# Ram_Upgrade.net
KiCad netlist of a schematic drawn in EAGLE
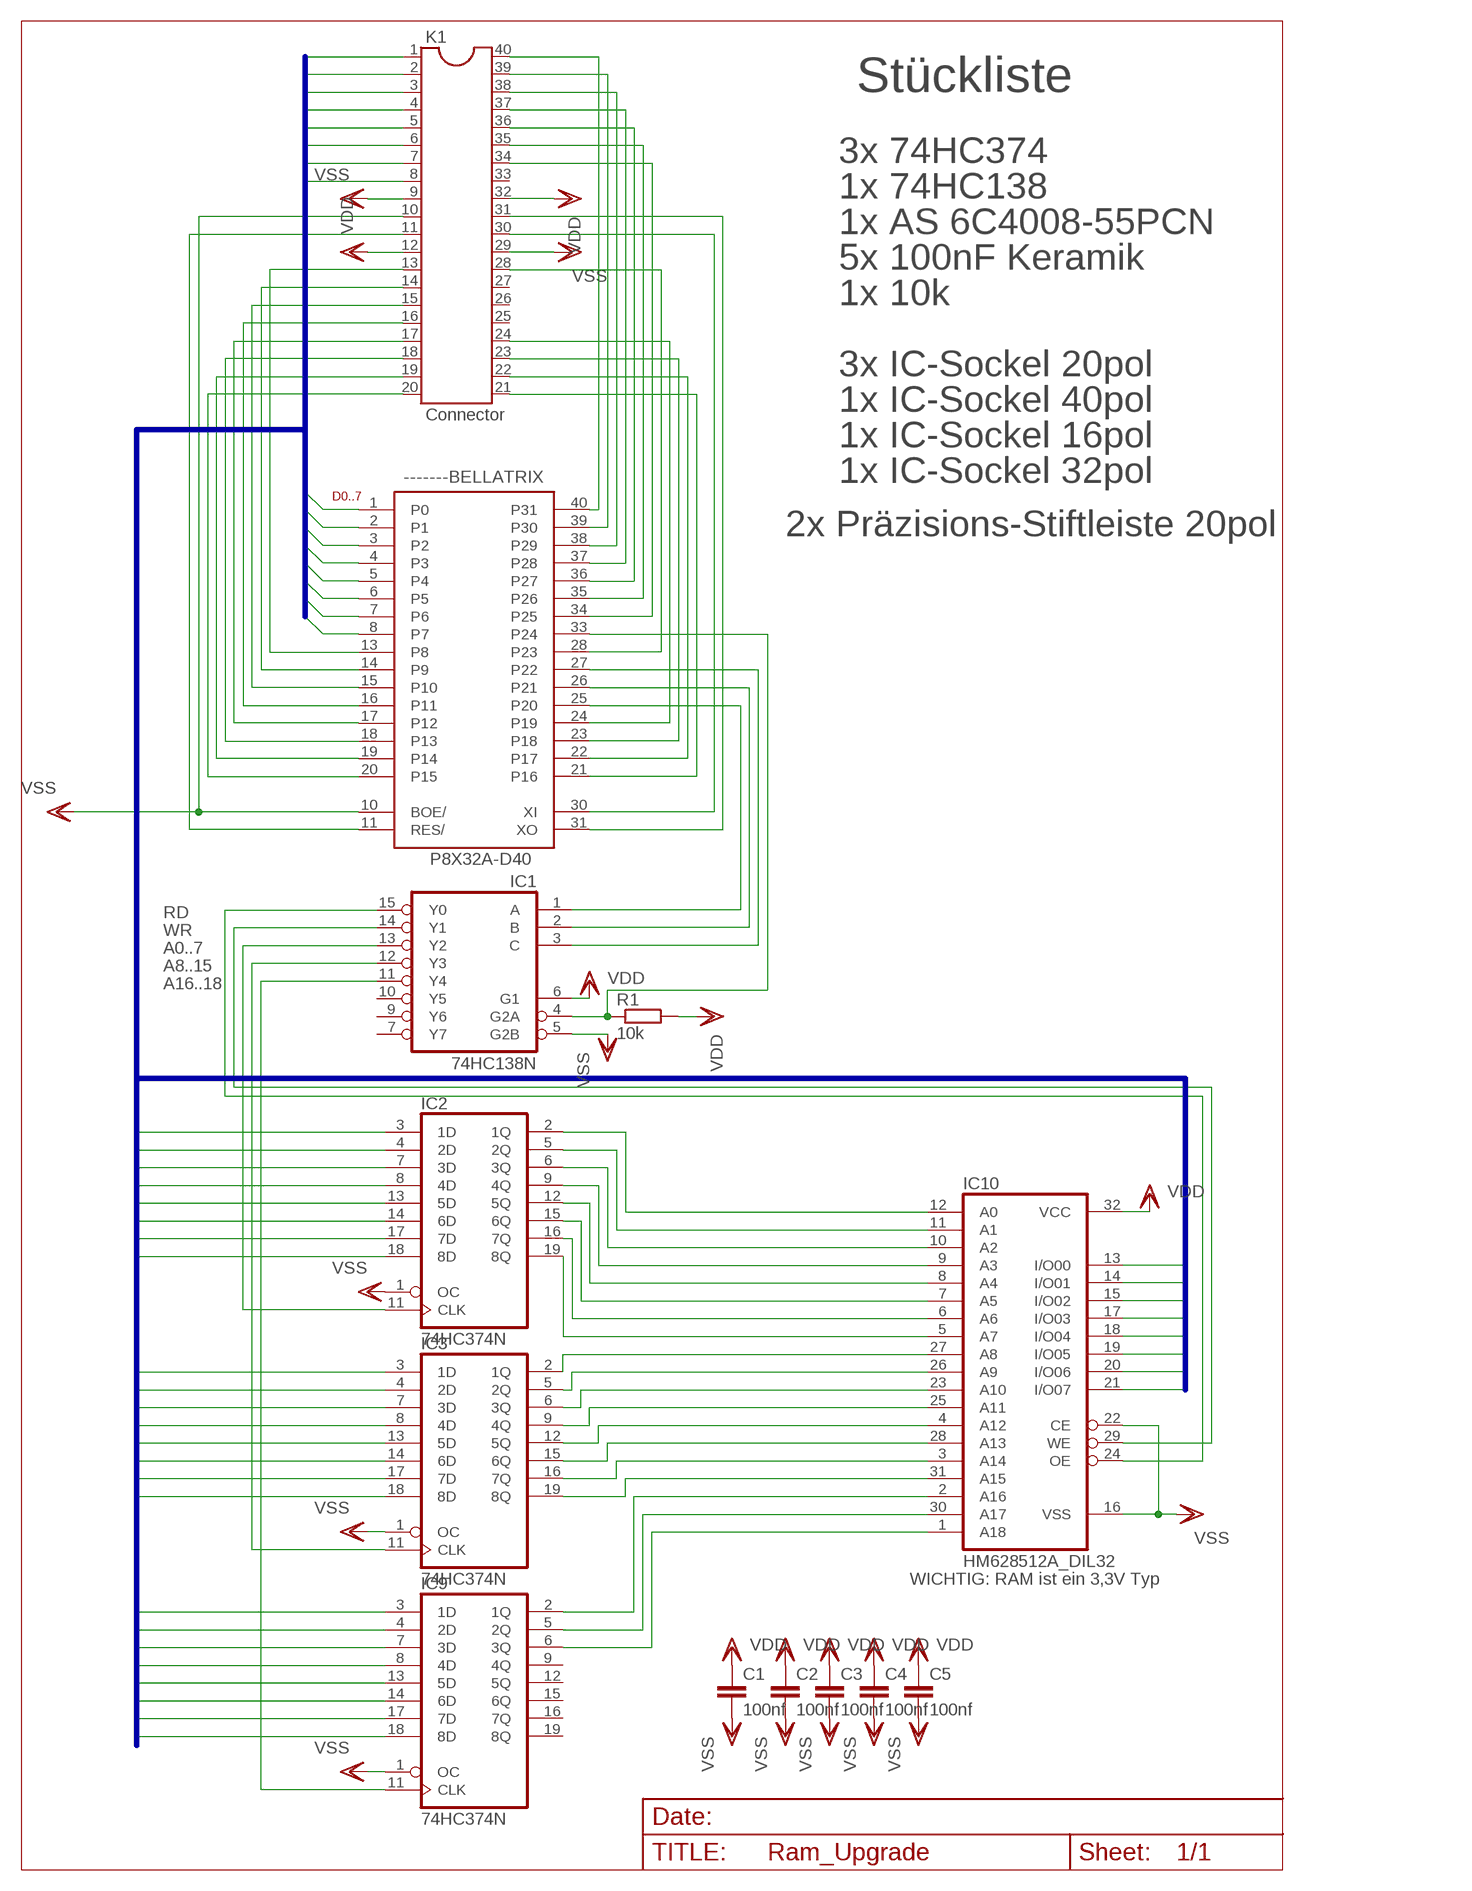
[diagram p0: schematic, sheet 1]

(export (version "E")
  (design (tool "Eeschema 10.0.6"))
  (components
    (comp (ref "-------BELLATRIX")
      (value "P8X32A-D40")
      (footprint "eagle-import:P8X32A-D40")
      (libsource (lib "eagle-import") (part "P8X32A-D40"))
    )
    (comp (ref "C1")
      (value "100nf")
      (footprint "eagle-import:C075-032X103")
      (libsource (lib "eagle-import") (part "C-EU075-032X103"))
    )
    (comp (ref "C2")
      (value "100nf")
      (footprint "eagle-import:C075-032X103")
      (libsource (lib "eagle-import") (part "C-EU075-032X103"))
    )
    (comp (ref "C3")
      (value "100nf")
      (footprint "eagle-import:C075-032X103")
      (libsource (lib "eagle-import") (part "C-EU075-032X103"))
    )
    (comp (ref "C4")
      (value "100nf")
      (footprint "eagle-import:C075-032X103")
      (libsource (lib "eagle-import") (part "C-EU075-032X103"))
    )
    (comp (ref "C5")
      (value "100nf")
      (footprint "eagle-import:C075-032X103")
      (libsource (lib "eagle-import") (part "C-EU075-032X103"))
    )
    (comp (ref "IC1")
      (value "74HC138N")
      (footprint "eagle-import:DIL16")
      (libsource (lib "eagle-import") (part "74138NHC"))
    )
    (comp (ref "IC2")
      (value "74HC374N")
      (footprint "eagle-import:DIL20")
      (libsource (lib "eagle-import") (part "74374NHC"))
    )
    (comp (ref "IC3")
      (value "74HC374N")
      (footprint "eagle-import:DIL20")
      (libsource (lib "eagle-import") (part "74374NHC"))
    )
    (comp (ref "IC9")
      (value "74HC374N")
      (footprint "eagle-import:DIL20")
      (libsource (lib "eagle-import") (part "74374NHC"))
    )
    (comp (ref "IC10")
      (value "HM628512A_DIL32")
      (footprint "eagle-import:DIL32")
      (libsource (lib "eagle-import") (part "HM628512A_DIL32"))
    )
    (comp (ref "K1")
      (value "Connector")
      (footprint "eagle-import:DIL40")
      (libsource (lib "eagle-import") (part "DIL40"))
    )
    (comp (ref "R1")
      (value "10k")
      (footprint "eagle-import:0207_10")
      (libsource (lib "eagle-import") (part "R-EU_0207/10"))
    )
  )
  (nets
    (net (code "1") (name "/D0") (class "Default")
      (node (ref "-------BELLATRIX") (pin "1") (pinfunction "P0_1") (pintype "bidirectional"))
      (node (ref "IC10") (pin "13") (pinfunction "I/O00_13") (pintype "bidirectional"))
      (node (ref "IC2") (pin "3") (pinfunction "1D_3") (pintype "input"))
      (node (ref "IC3") (pin "3") (pinfunction "1D_3") (pintype "input"))
      (node (ref "IC9") (pin "3") (pinfunction "1D_3") (pintype "input"))
      (node (ref "K1") (pin "1") (pinfunction "1_1") (pintype "passive"))
    )
    (net (code "2") (name "/D1") (class "Default")
      (node (ref "-------BELLATRIX") (pin "2") (pinfunction "P1_2") (pintype "bidirectional"))
      (node (ref "IC10") (pin "14") (pinfunction "I/O01_14") (pintype "bidirectional"))
      (node (ref "IC2") (pin "4") (pinfunction "2D_4") (pintype "input"))
      (node (ref "IC3") (pin "4") (pinfunction "2D_4") (pintype "input"))
      (node (ref "IC9") (pin "4") (pinfunction "2D_4") (pintype "input"))
      (node (ref "K1") (pin "2") (pinfunction "2_2") (pintype "passive"))
    )
    (net (code "3") (name "/D2") (class "Default")
      (node (ref "-------BELLATRIX") (pin "3") (pinfunction "P2_3") (pintype "bidirectional"))
      (node (ref "IC10") (pin "15") (pinfunction "I/O02_15") (pintype "bidirectional"))
      (node (ref "IC2") (pin "7") (pinfunction "3D_7") (pintype "input"))
      (node (ref "IC3") (pin "7") (pinfunction "3D_7") (pintype "input"))
      (node (ref "IC9") (pin "7") (pinfunction "3D_7") (pintype "input"))
      (node (ref "K1") (pin "3") (pinfunction "3_3") (pintype "passive"))
    )
    (net (code "4") (name "/D3") (class "Default")
      (node (ref "-------BELLATRIX") (pin "4") (pinfunction "P3_4") (pintype "bidirectional"))
      (node (ref "IC10") (pin "17") (pinfunction "I/O03_17") (pintype "bidirectional"))
      (node (ref "IC2") (pin "8") (pinfunction "4D_8") (pintype "input"))
      (node (ref "IC3") (pin "8") (pinfunction "4D_8") (pintype "input"))
      (node (ref "IC9") (pin "8") (pinfunction "4D_8") (pintype "input"))
      (node (ref "K1") (pin "4") (pinfunction "4_4") (pintype "passive"))
    )
    (net (code "5") (name "/D4") (class "Default")
      (node (ref "-------BELLATRIX") (pin "5") (pinfunction "P4_5") (pintype "bidirectional"))
      (node (ref "IC10") (pin "18") (pinfunction "I/O04_18") (pintype "bidirectional"))
      (node (ref "IC2") (pin "13") (pinfunction "5D_13") (pintype "input"))
      (node (ref "IC3") (pin "13") (pinfunction "5D_13") (pintype "input"))
      (node (ref "IC9") (pin "13") (pinfunction "5D_13") (pintype "input"))
      (node (ref "K1") (pin "5") (pinfunction "5_5") (pintype "passive"))
    )
    (net (code "6") (name "/D5") (class "Default")
      (node (ref "-------BELLATRIX") (pin "6") (pinfunction "P5_6") (pintype "bidirectional"))
      (node (ref "IC10") (pin "19") (pinfunction "I/O05_19") (pintype "bidirectional"))
      (node (ref "IC2") (pin "14") (pinfunction "6D_14") (pintype "input"))
      (node (ref "IC3") (pin "14") (pinfunction "6D_14") (pintype "input"))
      (node (ref "IC9") (pin "14") (pinfunction "6D_14") (pintype "input"))
      (node (ref "K1") (pin "6") (pinfunction "6_6") (pintype "passive"))
    )
    (net (code "7") (name "/D6") (class "Default")
      (node (ref "-------BELLATRIX") (pin "7") (pinfunction "P6_7") (pintype "bidirectional"))
      (node (ref "IC10") (pin "20") (pinfunction "I/O06_20") (pintype "bidirectional"))
      (node (ref "IC2") (pin "17") (pinfunction "7D_17") (pintype "input"))
      (node (ref "IC3") (pin "17") (pinfunction "7D_17") (pintype "input"))
      (node (ref "IC9") (pin "17") (pinfunction "7D_17") (pintype "input"))
      (node (ref "K1") (pin "7") (pinfunction "7_7") (pintype "passive"))
    )
    (net (code "8") (name "/D7") (class "Default")
      (node (ref "-------BELLATRIX") (pin "8") (pinfunction "P7_8") (pintype "bidirectional"))
      (node (ref "IC10") (pin "21") (pinfunction "I/O07_21") (pintype "bidirectional"))
      (node (ref "IC2") (pin "18") (pinfunction "8D_18") (pintype "input"))
      (node (ref "IC3") (pin "18") (pinfunction "8D_18") (pintype "input"))
      (node (ref "IC9") (pin "18") (pinfunction "8D_18") (pintype "input"))
      (node (ref "K1") (pin "8") (pinfunction "8_8") (pintype "passive"))
    )
    (net (code "9") (name "Net-(-------BELLATRIXB-P8)") (class "Default")
      (node (ref "-------BELLATRIX") (pin "13") (pinfunction "P8_13") (pintype "bidirectional"))
      (node (ref "K1") (pin "13") (pinfunction "13_13") (pintype "passive"))
    )
    (net (code "10") (name "Net-(-------BELLATRIXB-P9)") (class "Default")
      (node (ref "-------BELLATRIX") (pin "14") (pinfunction "P9_14") (pintype "bidirectional"))
      (node (ref "K1") (pin "14") (pinfunction "14_14") (pintype "passive"))
    )
    (net (code "11") (name "Net-(-------BELLATRIXB-P10)") (class "Default")
      (node (ref "-------BELLATRIX") (pin "15") (pinfunction "P10_15") (pintype "bidirectional"))
      (node (ref "K1") (pin "15") (pinfunction "15_15") (pintype "passive"))
    )
    (net (code "12") (name "Net-(-------BELLATRIXB-P11)") (class "Default")
      (node (ref "-------BELLATRIX") (pin "16") (pinfunction "P11_16") (pintype "bidirectional"))
      (node (ref "K1") (pin "16") (pinfunction "16_16") (pintype "passive"))
    )
    (net (code "13") (name "Net-(-------BELLATRIXB-P12)") (class "Default")
      (node (ref "-------BELLATRIX") (pin "17") (pinfunction "P12_17") (pintype "bidirectional"))
      (node (ref "K1") (pin "17") (pinfunction "17_17") (pintype "passive"))
    )
    (net (code "14") (name "Net-(-------BELLATRIXB-P13)") (class "Default")
      (node (ref "-------BELLATRIX") (pin "18") (pinfunction "P13_18") (pintype "bidirectional"))
      (node (ref "K1") (pin "18") (pinfunction "18_18") (pintype "passive"))
    )
    (net (code "15") (name "Net-(-------BELLATRIXB-P14)") (class "Default")
      (node (ref "-------BELLATRIX") (pin "19") (pinfunction "P14_19") (pintype "bidirectional"))
      (node (ref "K1") (pin "19") (pinfunction "19_19") (pintype "passive"))
    )
    (net (code "16") (name "Net-(-------BELLATRIXB-P15)") (class "Default")
      (node (ref "-------BELLATRIX") (pin "20") (pinfunction "P15_20") (pintype "bidirectional"))
      (node (ref "K1") (pin "20") (pinfunction "20_20") (pintype "passive"))
    )
    (net (code "17") (name "Net-(-------BELLATRIXB-P16)") (class "Default")
      (node (ref "-------BELLATRIX") (pin "21") (pinfunction "P16_21") (pintype "bidirectional"))
      (node (ref "K1") (pin "21") (pinfunction "21_21") (pintype "passive"))
    )
    (net (code "18") (name "Net-(-------BELLATRIXB-P17)") (class "Default")
      (node (ref "-------BELLATRIX") (pin "22") (pinfunction "P17_22") (pintype "bidirectional"))
      (node (ref "K1") (pin "22") (pinfunction "22_22") (pintype "passive"))
    )
    (net (code "19") (name "Net-(-------BELLATRIXB-P18)") (class "Default")
      (node (ref "-------BELLATRIX") (pin "23") (pinfunction "P18_23") (pintype "bidirectional"))
      (node (ref "K1") (pin "23") (pinfunction "23_23") (pintype "passive"))
    )
    (net (code "20") (name "Net-(-------BELLATRIXB-P19)") (class "Default")
      (node (ref "-------BELLATRIX") (pin "24") (pinfunction "P19_24") (pintype "bidirectional"))
      (node (ref "K1") (pin "24") (pinfunction "24_24") (pintype "passive"))
    )
    (net (code "21") (name "Net-(-------BELLATRIXB-P20)") (class "Default")
      (node (ref "-------BELLATRIX") (pin "25") (pinfunction "P20_25") (pintype "bidirectional"))
      (node (ref "IC1") (pin "1") (pinfunction "A_1") (pintype "input"))
    )
    (net (code "22") (name "Net-(-------BELLATRIXB-P21)") (class "Default")
      (node (ref "-------BELLATRIX") (pin "26") (pinfunction "P21_26") (pintype "bidirectional"))
      (node (ref "IC1") (pin "2") (pinfunction "B_2") (pintype "input"))
    )
    (net (code "23") (name "Net-(-------BELLATRIXB-P22)") (class "Default")
      (node (ref "-------BELLATRIX") (pin "27") (pinfunction "P22_27") (pintype "bidirectional"))
      (node (ref "IC1") (pin "3") (pinfunction "C_3") (pintype "input"))
    )
    (net (code "24") (name "Net-(-------BELLATRIXB-P23)") (class "Default")
      (node (ref "-------BELLATRIX") (pin "28") (pinfunction "P23_28") (pintype "bidirectional"))
      (node (ref "K1") (pin "28") (pinfunction "28_28") (pintype "passive"))
    )
    (net (code "25") (name "Net-(-------BELLATRIXB-P24)") (class "Default")
      (node (ref "-------BELLATRIX") (pin "33") (pinfunction "P24_33") (pintype "bidirectional"))
      (node (ref "IC1") (pin "4") (pinfunction "G2A_4") (pintype "input"))
      (node (ref "R1") (pin "1") (pinfunction "1_1") (pintype "passive"))
    )
    (net (code "26") (name "Net-(-------BELLATRIXB-P25)") (class "Default")
      (node (ref "-------BELLATRIX") (pin "34") (pinfunction "P25_34") (pintype "bidirectional"))
      (node (ref "K1") (pin "34") (pinfunction "34_34") (pintype "passive"))
    )
    (net (code "27") (name "Net-(-------BELLATRIXB-P26)") (class "Default")
      (node (ref "-------BELLATRIX") (pin "35") (pinfunction "P26_35") (pintype "bidirectional"))
      (node (ref "K1") (pin "35") (pinfunction "35_35") (pintype "passive"))
    )
    (net (code "28") (name "Net-(-------BELLATRIXB-P27)") (class "Default")
      (node (ref "-------BELLATRIX") (pin "36") (pinfunction "P27_36") (pintype "bidirectional"))
      (node (ref "K1") (pin "36") (pinfunction "36_36") (pintype "passive"))
    )
    (net (code "29") (name "Net-(-------BELLATRIXB-P28)") (class "Default")
      (node (ref "-------BELLATRIX") (pin "37") (pinfunction "P28_37") (pintype "bidirectional"))
      (node (ref "K1") (pin "37") (pinfunction "37_37") (pintype "passive"))
    )
    (net (code "30") (name "Net-(-------BELLATRIXB-P29)") (class "Default")
      (node (ref "-------BELLATRIX") (pin "38") (pinfunction "P29_38") (pintype "bidirectional"))
      (node (ref "K1") (pin "38") (pinfunction "38_38") (pintype "passive"))
    )
    (net (code "31") (name "Net-(-------BELLATRIXB-P30)") (class "Default")
      (node (ref "-------BELLATRIX") (pin "39") (pinfunction "P30_39") (pintype "bidirectional"))
      (node (ref "K1") (pin "39") (pinfunction "39_39") (pintype "passive"))
    )
    (net (code "32") (name "Net-(-------BELLATRIXB-P31)") (class "Default")
      (node (ref "-------BELLATRIX") (pin "40") (pinfunction "P31_40") (pintype "bidirectional"))
      (node (ref "K1") (pin "40") (pinfunction "40_40") (pintype "passive"))
    )
    (net (code "33") (name "Net-(-------BELLATRIXB-RES{slash})") (class "Default")
      (node (ref "-------BELLATRIX") (pin "11") (pinfunction "RES/_11") (pintype "bidirectional"))
      (node (ref "K1") (pin "11") (pinfunction "11_11") (pintype "passive"))
    )
    (net (code "34") (name "Net-(-------BELLATRIXB-XI)") (class "Default")
      (node (ref "-------BELLATRIX") (pin "30") (pinfunction "XI_30") (pintype "input"))
      (node (ref "K1") (pin "30") (pinfunction "30_30") (pintype "passive"))
    )
    (net (code "35") (name "Net-(-------BELLATRIXB-XO)") (class "Default")
      (node (ref "-------BELLATRIX") (pin "31") (pinfunction "XO_31") (pintype "output"))
      (node (ref "K1") (pin "31") (pinfunction "31_31") (pintype "passive"))
    )
    (net (code "36") (name "Net-(IC1A-Y2)") (class "Default")
      (node (ref "IC1") (pin "13") (pinfunction "Y2_13") (pintype "output"))
      (node (ref "IC2") (pin "11") (pinfunction "CLK_11") (pintype "input"))
    )
    (net (code "37") (name "Net-(IC1A-Y3)") (class "Default")
      (node (ref "IC1") (pin "12") (pinfunction "Y3_12") (pintype "output"))
      (node (ref "IC3") (pin "11") (pinfunction "CLK_11") (pintype "input"))
    )
    (net (code "38") (name "Net-(IC1A-Y4)") (class "Default")
      (node (ref "IC1") (pin "11") (pinfunction "Y4_11") (pintype "output"))
      (node (ref "IC9") (pin "11") (pinfunction "CLK_11") (pintype "input"))
    )
    (net (code "39") (name "Net-(IC10-A0)") (class "Default")
      (node (ref "IC10") (pin "12") (pinfunction "A0_12") (pintype "input"))
      (node (ref "IC2") (pin "2") (pinfunction "1Q_2") (pintype "tri_state"))
    )
    (net (code "40") (name "Net-(IC10-A1)") (class "Default")
      (node (ref "IC10") (pin "11") (pinfunction "A1_11") (pintype "input"))
      (node (ref "IC2") (pin "5") (pinfunction "2Q_5") (pintype "tri_state"))
    )
    (net (code "41") (name "Net-(IC10-A2)") (class "Default")
      (node (ref "IC10") (pin "10") (pinfunction "A2_10") (pintype "input"))
      (node (ref "IC2") (pin "6") (pinfunction "3Q_6") (pintype "tri_state"))
    )
    (net (code "42") (name "Net-(IC10-A3)") (class "Default")
      (node (ref "IC10") (pin "9") (pinfunction "A3_9") (pintype "input"))
      (node (ref "IC2") (pin "9") (pinfunction "4Q_9") (pintype "tri_state"))
    )
    (net (code "43") (name "Net-(IC10-A4)") (class "Default")
      (node (ref "IC10") (pin "8") (pinfunction "A4_8") (pintype "input"))
      (node (ref "IC2") (pin "12") (pinfunction "5Q_12") (pintype "tri_state"))
    )
    (net (code "44") (name "Net-(IC10-A5)") (class "Default")
      (node (ref "IC10") (pin "7") (pinfunction "A5_7") (pintype "input"))
      (node (ref "IC2") (pin "15") (pinfunction "6Q_15") (pintype "tri_state"))
    )
    (net (code "45") (name "Net-(IC10-A6)") (class "Default")
      (node (ref "IC10") (pin "6") (pinfunction "A6_6") (pintype "input"))
      (node (ref "IC2") (pin "16") (pinfunction "7Q_16") (pintype "tri_state"))
    )
    (net (code "46") (name "Net-(IC10-A7)") (class "Default")
      (node (ref "IC10") (pin "5") (pinfunction "A7_5") (pintype "input"))
      (node (ref "IC2") (pin "19") (pinfunction "8Q_19") (pintype "tri_state"))
    )
    (net (code "47") (name "Net-(IC10-A8)") (class "Default")
      (node (ref "IC10") (pin "27") (pinfunction "A8_27") (pintype "input"))
      (node (ref "IC3") (pin "2") (pinfunction "1Q_2") (pintype "tri_state"))
    )
    (net (code "48") (name "Net-(IC10-A9)") (class "Default")
      (node (ref "IC10") (pin "26") (pinfunction "A9_26") (pintype "input"))
      (node (ref "IC3") (pin "5") (pinfunction "2Q_5") (pintype "tri_state"))
    )
    (net (code "49") (name "Net-(IC10-A10)") (class "Default")
      (node (ref "IC10") (pin "23") (pinfunction "A10_23") (pintype "input"))
      (node (ref "IC3") (pin "6") (pinfunction "3Q_6") (pintype "tri_state"))
    )
    (net (code "50") (name "Net-(IC10-A11)") (class "Default")
      (node (ref "IC10") (pin "25") (pinfunction "A11_25") (pintype "input"))
      (node (ref "IC3") (pin "9") (pinfunction "4Q_9") (pintype "tri_state"))
    )
    (net (code "51") (name "Net-(IC10-A12)") (class "Default")
      (node (ref "IC10") (pin "4") (pinfunction "A12_4") (pintype "input"))
      (node (ref "IC3") (pin "12") (pinfunction "5Q_12") (pintype "tri_state"))
    )
    (net (code "52") (name "Net-(IC10-A13)") (class "Default")
      (node (ref "IC10") (pin "28") (pinfunction "A13_28") (pintype "input"))
      (node (ref "IC3") (pin "15") (pinfunction "6Q_15") (pintype "tri_state"))
    )
    (net (code "53") (name "Net-(IC10-A14)") (class "Default")
      (node (ref "IC10") (pin "3") (pinfunction "A14_3") (pintype "input"))
      (node (ref "IC3") (pin "16") (pinfunction "7Q_16") (pintype "tri_state"))
    )
    (net (code "54") (name "Net-(IC10-A15)") (class "Default")
      (node (ref "IC10") (pin "31") (pinfunction "A15_31") (pintype "input"))
      (node (ref "IC3") (pin "19") (pinfunction "8Q_19") (pintype "tri_state"))
    )
    (net (code "55") (name "Net-(IC10-A16)") (class "Default")
      (node (ref "IC10") (pin "2") (pinfunction "A16_2") (pintype "input"))
      (node (ref "IC9") (pin "2") (pinfunction "1Q_2") (pintype "tri_state"))
    )
    (net (code "56") (name "Net-(IC10-A17)") (class "Default")
      (node (ref "IC10") (pin "30") (pinfunction "A17_30") (pintype "input"))
      (node (ref "IC9") (pin "5") (pinfunction "2Q_5") (pintype "tri_state"))
    )
    (net (code "57") (name "Net-(IC10-A18)") (class "Default")
      (node (ref "IC10") (pin "1") (pinfunction "A18_1") (pintype "input"))
      (node (ref "IC9") (pin "6") (pinfunction "3Q_6") (pintype "tri_state"))
    )
    (net (code "58") (name "Net-(IC10-OE)") (class "Default")
      (node (ref "IC1") (pin "15") (pinfunction "Y0_15") (pintype "output"))
      (node (ref "IC10") (pin "24") (pinfunction "OE_24") (pintype "input"))
    )
    (net (code "59") (name "Net-(IC10-WE)") (class "Default")
      (node (ref "IC1") (pin "14") (pinfunction "Y1_14") (pintype "output"))
      (node (ref "IC10") (pin "29") (pinfunction "WE_29") (pintype "input"))
    )
    (net (code "60") (name "VDD") (class "Default")
      (node (ref "C1") (pin "1") (pinfunction "1_1") (pintype "passive"))
      (node (ref "C2") (pin "1") (pinfunction "1_1") (pintype "passive"))
      (node (ref "C3") (pin "1") (pinfunction "1_1") (pintype "passive"))
      (node (ref "C4") (pin "1") (pinfunction "1_1") (pintype "passive"))
      (node (ref "C5") (pin "1") (pinfunction "1_1") (pintype "passive"))
      (node (ref "IC1") (pin "6") (pinfunction "G1_6") (pintype "input"))
      (node (ref "IC10") (pin "32") (pinfunction "VCC_32") (pintype "power_in"))
      (node (ref "K1") (pin "12") (pinfunction "12_12") (pintype "passive"))
      (node (ref "K1") (pin "32") (pinfunction "32_32") (pintype "passive"))
      (node (ref "R1") (pin "2") (pinfunction "2_2") (pintype "passive"))
    )
    (net (code "61") (name "VSS") (class "Default")
      (node (ref "-------BELLATRIX") (pin "10") (pinfunction "BOE/_10") (pintype "input"))
      (node (ref "C1") (pin "2") (pinfunction "2_2") (pintype "passive"))
      (node (ref "C2") (pin "2") (pinfunction "2_2") (pintype "passive"))
      (node (ref "C3") (pin "2") (pinfunction "2_2") (pintype "passive"))
      (node (ref "C4") (pin "2") (pinfunction "2_2") (pintype "passive"))
      (node (ref "C5") (pin "2") (pinfunction "2_2") (pintype "passive"))
      (node (ref "IC1") (pin "5") (pinfunction "G2B_5") (pintype "input"))
      (node (ref "IC10") (pin "16") (pinfunction "VSS_16") (pintype "power_in"))
      (node (ref "IC10") (pin "22") (pinfunction "CE_22") (pintype "input"))
      (node (ref "IC2") (pin "1") (pinfunction "OC_1") (pintype "input"))
      (node (ref "IC3") (pin "1") (pinfunction "OC_1") (pintype "input"))
      (node (ref "IC9") (pin "1") (pinfunction "OC_1") (pintype "input"))
      (node (ref "K1") (pin "10") (pinfunction "10_10") (pintype "passive"))
      (node (ref "K1") (pin "29") (pinfunction "29_29") (pintype "passive"))
      (node (ref "K1") (pin "9") (pinfunction "9_9") (pintype "passive"))
    )
    (net (code "62") (name "unconnected-(IC1A-Y5-Pad10)") (class "Default")
      (node (ref "IC1") (pin "10") (pinfunction "Y5_10") (pintype "output"))
    )
    (net (code "63") (name "unconnected-(IC1A-Y6-Pad9)") (class "Default")
      (node (ref "IC1") (pin "9") (pinfunction "Y6_9") (pintype "output"))
    )
    (net (code "64") (name "unconnected-(IC1A-Y7-Pad7)") (class "Default")
      (node (ref "IC1") (pin "7") (pinfunction "Y7_7") (pintype "output"))
    )
    (net (code "65") (name "unconnected-(IC9A-4Q-Pad9)") (class "Default")
      (node (ref "IC9") (pin "9") (pinfunction "4Q_9") (pintype "tri_state"))
    )
    (net (code "66") (name "unconnected-(IC9A-5Q-Pad12)") (class "Default")
      (node (ref "IC9") (pin "12") (pinfunction "5Q_12") (pintype "tri_state"))
    )
    (net (code "67") (name "unconnected-(IC9A-6Q-Pad15)") (class "Default")
      (node (ref "IC9") (pin "15") (pinfunction "6Q_15") (pintype "tri_state"))
    )
    (net (code "68") (name "unconnected-(IC9A-7Q-Pad16)") (class "Default")
      (node (ref "IC9") (pin "16") (pinfunction "7Q_16") (pintype "tri_state"))
    )
    (net (code "69") (name "unconnected-(IC9A-8Q-Pad19)") (class "Default")
      (node (ref "IC9") (pin "19") (pinfunction "8Q_19") (pintype "tri_state"))
    )
    (net (code "70") (name "unconnected-(K1-Pad25)") (class "Default")
      (node (ref "K1") (pin "25") (pinfunction "25_25") (pintype "passive"))
    )
    (net (code "71") (name "unconnected-(K1-Pad26)") (class "Default")
      (node (ref "K1") (pin "26") (pinfunction "26_26") (pintype "passive"))
    )
    (net (code "72") (name "unconnected-(K1-Pad27)") (class "Default")
      (node (ref "K1") (pin "27") (pinfunction "27_27") (pintype "passive"))
    )
    (net (code "73") (name "unconnected-(K1-Pad33)") (class "Default")
      (node (ref "K1") (pin "33") (pinfunction "33_33") (pintype "passive"))
    )
  )
)
